# lm317.net
KiCad netlist of a schematic drawn in EAGLE
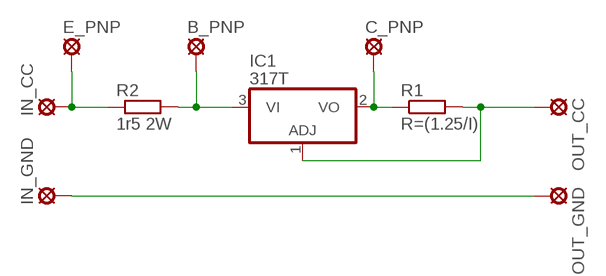
[diagram p0: schematic, sheet 1]

(export (version "E")
  (design (tool "Eeschema 10.0.6"))
  (components
    (comp (ref "B_PNP")
      (value "SE14")
      (footprint "eagle-import:SE14")
      (libsource (lib "eagle-import") (part "SE14"))
    )
    (comp (ref "C_PNP")
      (value "SE14")
      (footprint "eagle-import:SE14")
      (libsource (lib "eagle-import") (part "SE14"))
    )
    (comp (ref "E_PNP")
      (value "SE14")
      (footprint "eagle-import:SE14")
      (libsource (lib "eagle-import") (part "SE14"))
    )
    (comp (ref "IC1")
      (value "317T")
      (footprint "eagle-import:TO220H")
      (libsource (lib "eagle-import") (part "317T"))
    )
    (comp (ref "IN_CC")
      (value "SE14")
      (footprint "eagle-import:SE14")
      (libsource (lib "eagle-import") (part "SE14"))
    )
    (comp (ref "IN_GND")
      (value "SE14")
      (footprint "eagle-import:SE14")
      (libsource (lib "eagle-import") (part "SE14"))
    )
    (comp (ref "OUT_CC")
      (value "SE14")
      (footprint "eagle-import:SE14")
      (libsource (lib "eagle-import") (part "SE14"))
    )
    (comp (ref "OUT_GND")
      (value "SE14")
      (footprint "eagle-import:SE14")
      (libsource (lib "eagle-import") (part "SE14"))
    )
    (comp (ref "R1")
      (value "R=(1.25/I)")
      (footprint "eagle-import:0617_22")
      (libsource (lib "eagle-import") (part "R-EU_0617/22"))
    )
    (comp (ref "R2")
      (value "1r5 2W")
      (footprint "eagle-import:0617_22")
      (libsource (lib "eagle-import") (part "R-EU_0617/22"))
    )
  )
  (nets
    (net (code "1") (name "Net-(E_PNP-PadMP)") (class "Default")
      (node (ref "E_PNP") (pin "MP") (pinfunction "MP_MP") (pintype "passive"))
      (node (ref "IN_CC") (pin "MP") (pinfunction "MP_MP") (pintype "passive"))
      (node (ref "R2") (pin "1") (pinfunction "1_1") (pintype "passive"))
    )
    (net (code "2") (name "Net-(IC1-ADJ)") (class "Default")
      (node (ref "IC1") (pin "1") (pinfunction "ADJ_1") (pintype "input"))
      (node (ref "OUT_CC") (pin "MP") (pinfunction "MP_MP") (pintype "passive"))
      (node (ref "R1") (pin "2") (pinfunction "2_2") (pintype "passive"))
    )
    (net (code "3") (name "Net-(IC1-VI)") (class "Default")
      (node (ref "B_PNP") (pin "MP") (pinfunction "MP_MP") (pintype "passive"))
      (node (ref "IC1") (pin "3") (pinfunction "VI_3") (pintype "input"))
      (node (ref "R2") (pin "2") (pinfunction "2_2") (pintype "passive"))
    )
    (net (code "4") (name "Net-(IC1-VO)") (class "Default")
      (node (ref "C_PNP") (pin "MP") (pinfunction "MP_MP") (pintype "passive"))
      (node (ref "IC1") (pin "2") (pinfunction "VO_2") (pintype "passive"))
      (node (ref "R1") (pin "1") (pinfunction "1_1") (pintype "passive"))
    )
    (net (code "5") (name "Net-(IN_GND-PadMP)") (class "Default")
      (node (ref "IN_GND") (pin "MP") (pinfunction "MP_MP") (pintype "passive"))
      (node (ref "OUT_GND") (pin "MP") (pinfunction "MP_MP") (pintype "passive"))
    )
  )
)
